# BREW_MONITOR.net
KiCad netlist of a schematic drawn in Altium Designer
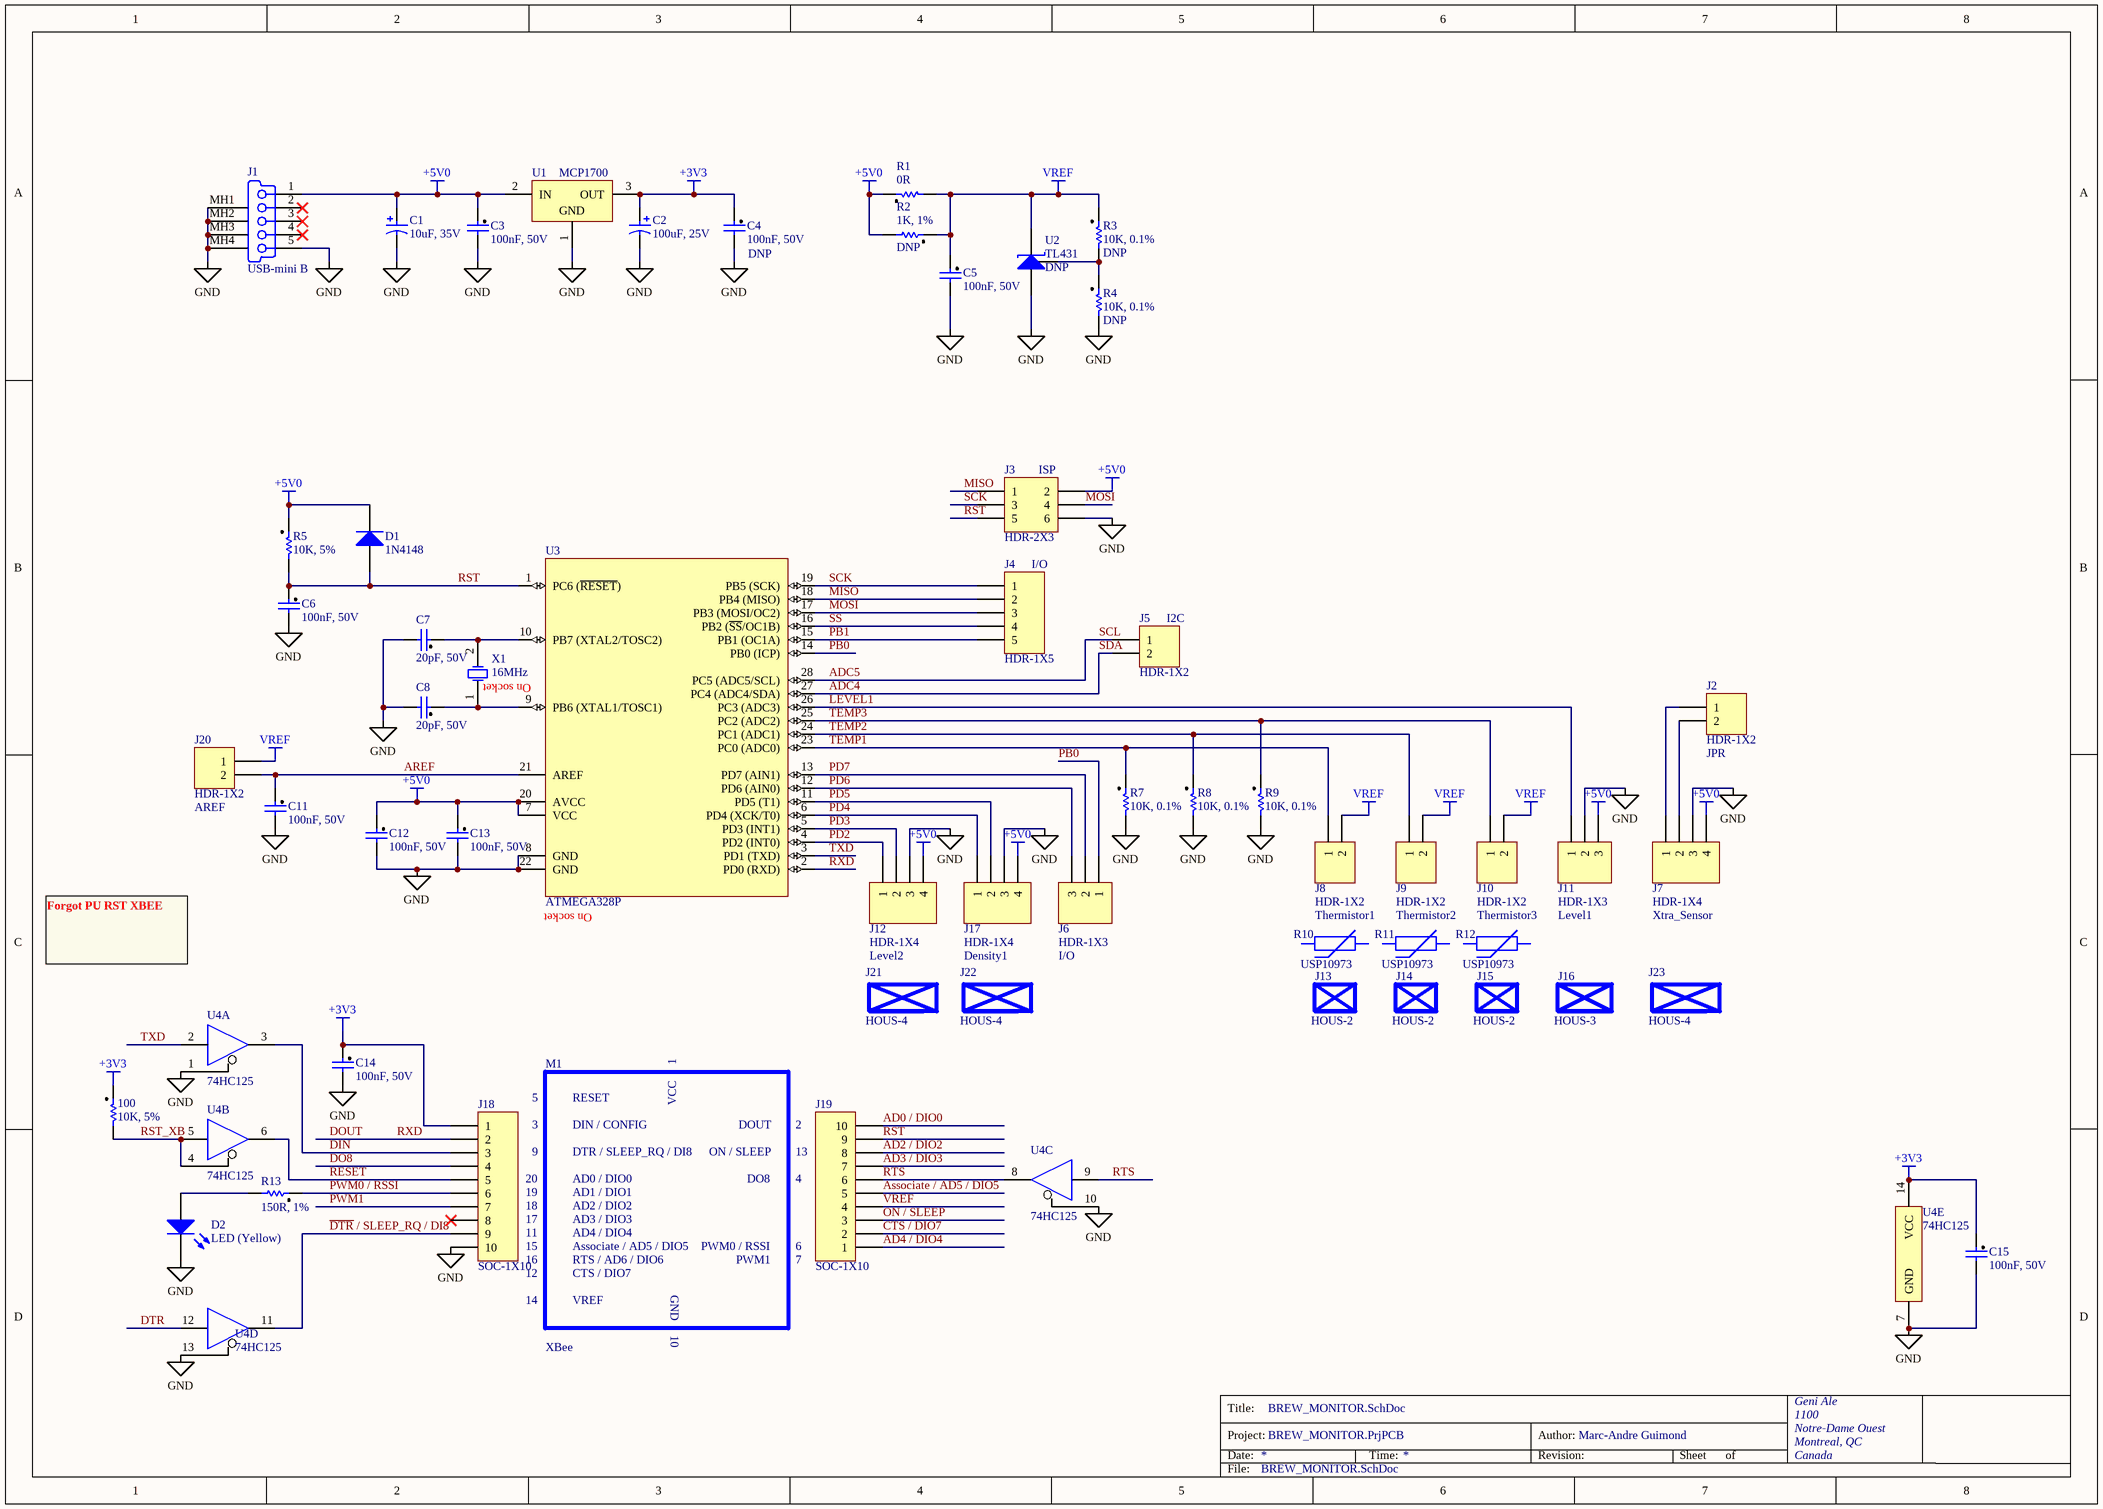
[diagram p0: BREW_MONITOR.SchDoc]

(export (version "E")
  (design (tool "Eeschema 10.0.6"))
  (components
    (comp (ref "100")
      (value "10K, 5%")
      (footprint "0805 (2012 Metric)")
      (description "RES 10K OHM 1/8W 5% 0805")
      (fields (field (name "MANUFACTURER") "Stackpole Electronics Inc") (field (name "TOLERANCE") "5%"))
      (libsource (lib "GRR_Resistor") (part "RMCF0805JT10K0"))
    )
    (comp (ref "C1")
      (value "10uF, 35V")
      (footprint "CAP_RAD-2.0")
      (description "CAP ALUM 10UF 35V 20% RADIAL")
      (fields (field (name "MANUFACTURER") "Kemet") (field (name "VOLTAGE") "35V"))
      (libsource (lib "GRR_Capacitor") (part "ESK106M035AC3AA"))
    )
    (comp (ref "C2")
      (value "100uF, 25V")
      (footprint "CAP_RAD-2.0")
      (description "CAP ALUM 100UF 25V 20% RADIAL")
      (fields (field (name "MANUFACTURER") "Kemet") (field (name "VOLTAGE") "25V"))
      (libsource (lib "GRR_Capacitor") (part "ESK107M025AC3AA"))
    )
    (comp (ref "C3")
      (value "100nF, 50V")
      (footprint "0805 (2012 Metric)")
      (description "CAP CER 0.1UF 50V 10% X7R 0805")
      (fields (field (name "MANUFACTURER") "TDK Corporation") (field (name "VOLTAGE") "50V"))
      (libsource (lib "GRR_Capacitor") (part "C2012X7R1H104K085AA"))
    )
    (comp (ref "C4")
      (value "100nF, 50V")
      (footprint "0805 (2012 Metric)")
      (description "CAP CER 0.1UF 50V 10% X7R 0805")
      (fields
        (field (name "MANUFACTURER") "TDK Corporation")
        (field (name "VOLTAGE") "50V")
        (field (name "POPULATE") "DNP")
      )
      (libsource (lib "GRR_Capacitor") (part "C2012X7R1H104K085AA"))
    )
    (comp (ref "C5")
      (value "100nF, 50V")
      (footprint "0805 (2012 Metric)")
      (description "CAP CER 0.1UF 50V 10% X7R 0805")
      (fields (field (name "MANUFACTURER") "TDK Corporation") (field (name "VOLTAGE") "50V"))
      (libsource (lib "GRR_Capacitor") (part "C2012X7R1H104K085AA"))
    )
    (comp (ref "C6")
      (value "100nF, 50V")
      (footprint "0805 (2012 Metric)")
      (description "CAP CER 0.1UF 50V 10% X7R 0805")
      (fields (field (name "MANUFACTURER") "TDK Corporation") (field (name "VOLTAGE") "50V"))
      (libsource (lib "GRR_Capacitor") (part "C2012X7R1H104K085AA"))
    )
    (comp (ref "C7")
      (value "20pF, 50V")
      (footprint "0603 (1608 Metric)")
      (description "CAP CER 20PF 50V 5% NPO 0603")
      (fields (field (name "MANUFACTURER") "Yageo") (field (name "VOLTAGE") "50V"))
      (libsource (lib "GRR_Capacitor") (part "CC0603JRNPO9BN200"))
    )
    (comp (ref "C8")
      (value "20pF, 50V")
      (footprint "0603 (1608 Metric)")
      (description "CAP CER 20PF 50V 5% NPO 0603")
      (fields (field (name "MANUFACTURER") "Yageo") (field (name "VOLTAGE") "50V"))
      (libsource (lib "GRR_Capacitor") (part "CC0603JRNPO9BN200"))
    )
    (comp (ref "C11")
      (value "100nF, 50V")
      (footprint "0805 (2012 Metric)")
      (description "CAP CER 0.1UF 50V 10% X7R 0805")
      (fields (field (name "MANUFACTURER") "TDK Corporation") (field (name "VOLTAGE") "50V"))
      (libsource (lib "GRR_Capacitor") (part "C2012X7R1H104K085AA"))
    )
    (comp (ref "C12")
      (value "100nF, 50V")
      (footprint "0805 (2012 Metric)")
      (description "CAP CER 0.1UF 50V 10% X7R 0805")
      (fields (field (name "MANUFACTURER") "TDK Corporation") (field (name "VOLTAGE") "50V"))
      (libsource (lib "GRR_Capacitor") (part "C2012X7R1H104K085AA"))
    )
    (comp (ref "C13")
      (value "100nF, 50V")
      (footprint "0805 (2012 Metric)")
      (description "CAP CER 0.1UF 50V 10% X7R 0805")
      (fields (field (name "MANUFACTURER") "TDK Corporation") (field (name "VOLTAGE") "50V"))
      (libsource (lib "GRR_Capacitor") (part "C2012X7R1H104K085AA"))
    )
    (comp (ref "C14")
      (value "100nF, 50V")
      (footprint "0805 (2012 Metric)")
      (description "CAP CER 0.1UF 50V 10% X7R 0805")
      (fields (field (name "MANUFACTURER") "TDK Corporation") (field (name "VOLTAGE") "50V"))
      (libsource (lib "GRR_Capacitor") (part "C2012X7R1H104K085AA"))
    )
    (comp (ref "C15")
      (value "100nF, 50V")
      (footprint "0805 (2012 Metric)")
      (description "CAP CER 0.1UF 50V 10% X7R 0805")
      (fields (field (name "MANUFACTURER") "TDK Corporation") (field (name "VOLTAGE") "50V"))
      (libsource (lib "GRR_Capacitor") (part "C2012X7R1H104K085AA"))
    )
    (comp (ref "D1")
      (value "1N4148")
      (footprint "DO-35")
      (description "DIODE SMALL SIG 100V 0.2A DO35")
      (fields (field (name "MANUFACTURER") "Fairchild Semiconductor"))
      (libsource (lib "GRR_Diode") (part "1N4148TACT"))
    )
    (comp (ref "D2")
      (value "LED (Yellow)")
      (footprint "LED-1")
      (description "LED 5MM YELLOW DIFFUSED")
      (fields (field (name "MANUFACTURER") "Lite-On Inc"))
      (libsource (lib "GRR_LED") (part "LTL-307Y"))
    )
    (comp (ref "J1")
      (value "USB-mini B")
      (footprint "CON_USB-UX60SC")
      (description "CONN RCPT USB MINI B R/A SMD")
      (fields (field (name "MANUFACTURER") "Hirose Electric Co Ltd"))
      (libsource (lib "GRR_Connector") (part "UX60SC-MB-5ST(80)"))
    )
    (comp (ref "J2")
      (value "HDR-1X2")
      (footprint "HDR1X2")
      (description "CONN HEADER .100\" SNGL STR 2POS")
      (fields (field (name "MANUFACTURER") "Sullins Connector Solutions") (field (name "REF") "JPR"))
      (libsource (lib "GRR_Connector") (part "PRPC002SAAN-RC"))
    )
    (comp (ref "J3")
      (value "HDR-2X3")
      (footprint "HDR2X3")
      (description "JUMPER PLUG 6POS DOUBLE ROW")
      (fields (field (name "MANUFACTURER") "Omron Electronics Inc-EMC Div"))
      (libsource (lib "GRR_Connector") (part "XG8T-0631"))
    )
    (comp (ref "J4")
      (value "HDR-1X5")
      (footprint "HDR1X5")
      (description "CONN HEADER .100\" SNGL STR 5POS")
      (fields (field (name "MANUFACTURER") "Sullins Connector Solutions") (field (name "REF") "I/O"))
      (libsource (lib "GRR_Connector") (part "PRPC005SAAN-RC"))
    )
    (comp (ref "J5")
      (value "HDR-1X2")
      (footprint "HDR1X2")
      (description "CONN HEADER .100\" SNGL STR 2POS")
      (fields (field (name "MANUFACTURER") "Sullins Connector Solutions") (field (name "REF") "I2C"))
      (libsource (lib "GRR_Connector") (part "PRPC002SAAN-RC"))
    )
    (comp (ref "J6")
      (value "HDR-1X3")
      (footprint "HDR1X3")
      (description "CONN HEADER .100\" SNGL STR 3POS")
      (fields (field (name "MANUFACTURER") "Sullins Connector Solutions") (field (name "REF") "I/O"))
      (libsource (lib "GRR_Connector") (part "PRPC003SAAN-RC"))
    )
    (comp (ref "J7")
      (value "HDR-1X4")
      (footprint "HDR1X4_RA POL_SHR_TE")
      (description "CONN HEADER RTANG 4POS .100 TIN")
      (fields (field (name "MANUFACTURER") "TE Connectivity") (field (name "REF") "Xtra_Sensor"))
      (libsource (lib "GRR_Connector") (part "2-644488-4"))
    )
    (comp (ref "J8")
      (value "HDR-1X2")
      (footprint "HDR1X2_RA POL_SHR_TE")
      (description "CONN HEADER RTANG 2POS .100 TIN")
      (fields (field (name "MANUFACTURER") "TE Connectivity") (field (name "REF") "Thermistor1"))
      (libsource (lib "GRR_Connector") (part "2-644488-2"))
    )
    (comp (ref "J9")
      (value "HDR-1X2")
      (footprint "HDR1X2_RA POL_SHR_TE")
      (description "CONN HEADER RTANG 2POS .100 TIN")
      (fields (field (name "MANUFACTURER") "TE Connectivity") (field (name "REF") "Thermistor2"))
      (libsource (lib "GRR_Connector") (part "2-644488-2"))
    )
    (comp (ref "J10")
      (value "HDR-1X2")
      (footprint "HDR1X2_RA POL_SHR_TE")
      (description "CONN HEADER RTANG 2POS .100 TIN")
      (fields (field (name "MANUFACTURER") "TE Connectivity") (field (name "REF") "Thermistor3"))
      (libsource (lib "GRR_Connector") (part "2-644488-2"))
    )
    (comp (ref "J11")
      (value "HDR-1X3")
      (footprint "HDR1X3_RA POL_SHR_TE")
      (description "CONN HEADER RTANG 3POS .100 TIN")
      (fields (field (name "MANUFACTURER") "TE Connectivity") (field (name "REF") "Level1"))
      (libsource (lib "GRR_Connector") (part "2-644488-3"))
    )
    (comp (ref "J12")
      (value "HDR-1X4")
      (footprint "HDR1X4_RA POL_SHR_TE")
      (description "CONN HEADER RTANG 4POS .100 TIN")
      (fields (field (name "MANUFACTURER") "TE Connectivity") (field (name "REF") "Level2"))
      (libsource (lib "GRR_Connector") (part "2-644488-4"))
    )
    (comp (ref "J13")
      (value "HOUS-2")
      (footprint "NO_FOOT")
      (description "CONN RCPT 2POS 22AWG POL MTA100")
      (fields (field (name "MANUFACTURER") "TE Connectivity"))
      (libsource (lib "GRR_CrimpTerminal") (part "3-644083-2"))
    )
    (comp (ref "J14")
      (value "HOUS-2")
      (footprint "NO_FOOT")
      (description "CONN RCPT 2POS 22AWG POL MTA100")
      (fields (field (name "MANUFACTURER") "TE Connectivity"))
      (libsource (lib "GRR_CrimpTerminal") (part "3-644083-2"))
    )
    (comp (ref "J15")
      (value "HOUS-2")
      (footprint "NO_FOOT")
      (description "CONN RCPT 2POS 22AWG POL MTA100")
      (fields (field (name "MANUFACTURER") "TE Connectivity"))
      (libsource (lib "GRR_CrimpTerminal") (part "3-644083-2"))
    )
    (comp (ref "J16")
      (value "HOUS-3")
      (footprint "NO_FOOT")
      (description "CONN RCPT 3POS 22AWG POL MTA100")
      (fields (field (name "MANUFACTURER") "TE Connectivity"))
      (libsource (lib "GRR_CrimpTerminal") (part "3-644083-3"))
    )
    (comp (ref "J17")
      (value "HDR-1X4")
      (footprint "HDR1X4_RA POL_SHR_TE")
      (description "CONN HEADER RTANG 4POS .100 TIN")
      (fields (field (name "MANUFACTURER") "TE Connectivity") (field (name "REF") "Density1"))
      (libsource (lib "GRR_Connector") (part "2-644488-4"))
    )
    (comp (ref "J18")
      (value "SOC-1X10")
      (footprint "SOC1X10 2MM")
      (description "CONN SOCKET 10POS 2MM VERT T/H")
      (fields (field (name "MANUFACTURER") "3M"))
      (libsource (lib "GRR_Connector") (part "950510-6102-AR"))
    )
    (comp (ref "J19")
      (value "SOC-1X10")
      (footprint "SOC1X10 2MM")
      (description "CONN SOCKET 10POS 2MM VERT T/H")
      (fields (field (name "MANUFACTURER") "3M"))
      (libsource (lib "") (part "950510-6102-AR_1"))
    )
    (comp (ref "J20")
      (value "HDR-1X2")
      (footprint "HDR1X2")
      (description "CONN HEADER .100\" SNGL STR 2POS")
      (fields (field (name "MANUFACTURER") "Sullins Connector Solutions") (field (name "REF") "AREF"))
      (libsource (lib "") (part "PRPC002SAAN-RC_1"))
    )
    (comp (ref "J21")
      (value "HOUS-4")
      (footprint "NO_FOOT")
      (description "CONN RCPT 4POS 22AWG POL MTA100")
      (fields (field (name "MANUFACTURER") "TE Connectivity"))
      (libsource (lib "GRR_CrimpTerminal") (part "3-644083-4"))
    )
    (comp (ref "J22")
      (value "HOUS-4")
      (footprint "NO_FOOT")
      (description "CONN RCPT 4POS 22AWG POL MTA100")
      (fields (field (name "MANUFACTURER") "TE Connectivity"))
      (libsource (lib "GRR_CrimpTerminal") (part "3-644083-4"))
    )
    (comp (ref "J23")
      (value "HOUS-4")
      (footprint "NO_FOOT")
      (description "CONN RCPT 4POS 22AWG POL MTA100")
      (fields (field (name "MANUFACTURER") "TE Connectivity"))
      (libsource (lib "GRR_CrimpTerminal") (part "3-644083-4"))
    )
    (comp (ref "M1")
      (value "XBee")
      (footprint "XBee-20")
      (description "MODULE 802.15.4 1MW W/WIRE ANT")
      (fields (field (name "MANUFACTURER") "Digi International/Maxstream"))
      (libsource (lib "GRR_RF") (part "XB24-AWI-001"))
    )
    (comp (ref "R1")
      (value "0R")
      (footprint "JPR-0.2")
      (description "RES 0R")
      (fields (field (name "POWER") "0.333W, 1/3W"))
      (libsource (lib "GRR_Resistor") (part "JUMPER"))
    )
    (comp (ref "R2")
      (value "1K, 1%")
      (footprint "0805 (2012 Metric)")
      (description "RES 1K OHM 1/8W 1% 0805")
      (fields
        (field (name "MANUFACTURER") "Stackpole Electronics Inc")
        (field (name "TOLERANCE") "1%")
        (field (name "POPULATE") "DNP")
      )
      (libsource (lib "GRR_Resistor") (part "RMCF0805FT1K00"))
    )
    (comp (ref "R3")
      (value "10K, 0.1%")
      (footprint "0805 (2012 Metric)")
      (description "RES 10K OHM 1/8W .1% 0805 SMD")
      (fields
        (field (name "MANUFACTURER") "Bourns Inc.")
        (field (name "TOLERANCE") "0.1%")
        (field (name "POPULATE") "DNP")
      )
      (libsource (lib "GRR_Resistor") (part "CRT0805-BY-1002ELF"))
    )
    (comp (ref "R4")
      (value "10K, 0.1%")
      (footprint "0805 (2012 Metric)")
      (description "RES 10K OHM 1/8W .1% 0805 SMD")
      (fields
        (field (name "MANUFACTURER") "Bourns Inc.")
        (field (name "TOLERANCE") "0.1%")
        (field (name "POPULATE") "DNP")
      )
      (libsource (lib "GRR_Resistor") (part "CRT0805-BY-1002ELF"))
    )
    (comp (ref "R5")
      (value "10K, 5%")
      (footprint "0805 (2012 Metric)")
      (description "RES 10K OHM 1/8W 5% 0805")
      (fields (field (name "MANUFACTURER") "Stackpole Electronics Inc") (field (name "TOLERANCE") "5%"))
      (libsource (lib "GRR_Resistor") (part "RMCF0805JT10K0"))
    )
    (comp (ref "R7")
      (value "10K, 0.1%")
      (footprint "0805 (2012 Metric)")
      (description "RES 10K OHM 1/8W .1% 0805 SMD")
      (fields (field (name "MANUFACTURER") "Bourns Inc.") (field (name "TOLERANCE") "0.1%"))
      (libsource (lib "GRR_Resistor") (part "CRT0805-BY-1002ELF"))
    )
    (comp (ref "R8")
      (value "10K, 0.1%")
      (footprint "0805 (2012 Metric)")
      (description "RES 10K OHM 1/8W .1% 0805 SMD")
      (fields (field (name "MANUFACTURER") "Bourns Inc.") (field (name "TOLERANCE") "0.1%"))
      (libsource (lib "GRR_Resistor") (part "CRT0805-BY-1002ELF"))
    )
    (comp (ref "R9")
      (value "10K, 0.1%")
      (footprint "0805 (2012 Metric)")
      (description "RES 10K OHM 1/8W .1% 0805 SMD")
      (fields (field (name "MANUFACTURER") "Bourns Inc.") (field (name "TOLERANCE") "0.1%"))
      (libsource (lib "GRR_Resistor") (part "CRT0805-BY-1002ELF"))
    )
    (comp (ref "R10")
      (value "USP10973")
      (footprint "NO_FOOT")
      (description "THERMISTOR ASSEMBLY 10K OHM")
      (fields (field (name "MANUFACTURER") "US Sensor") (field (name "TOLERANCE") "±1%"))
      (libsource (lib "GRR_Sensor") (part "USP10973"))
    )
    (comp (ref "R11")
      (value "USP10973")
      (footprint "NO_FOOT")
      (description "THERMISTOR ASSEMBLY 10K OHM")
      (fields (field (name "MANUFACTURER") "US Sensor") (field (name "TOLERANCE") "±1%"))
      (libsource (lib "GRR_Sensor") (part "USP10973"))
    )
    (comp (ref "R12")
      (value "USP10973")
      (footprint "NO_FOOT")
      (description "THERMISTOR ASSEMBLY 10K OHM")
      (fields (field (name "MANUFACTURER") "US Sensor") (field (name "TOLERANCE") "±1%"))
      (libsource (lib "GRR_Sensor") (part "USP10973"))
    )
    (comp (ref "R13")
      (value "150R, 1%")
      (footprint "0805 (2012 Metric)")
      (description "RES 150 OHM 1/8W 1% 0805")
      (fields (field (name "MANUFACTURER") "Stackpole Electronics Inc") (field (name "TOLERANCE") "1%"))
      (libsource (lib "GRR_Resistor") (part "RMCF0805FT150R"))
    )
    (comp (ref "U1")
      (value "MCP1700")
      (footprint "TO-92A_L")
      (description "IC REG LDO 3.3V 0.25A TO92-3")
      (fields (field (name "MANUFACTURER") "Microchip Technology"))
      (libsource (lib "GRR_PMIC") (part "MCP1700-3302E/TO"))
    )
    (comp (ref "U2")
      (value "TL431")
      (footprint "TO-92A_L")
      (description "IC VREF SHUNT PREC ADJ TO-92-3")
      (fields
        (field (name "MANUFACTURER") "STMicroelectronics")
        (field (name "TOLERANCE") "±2%")
        (field (name "POPULATE") "DNP")
      )
      (libsource (lib "GRR_PMIC") (part "TL431CZ"))
    )
    (comp (ref "U3")
      (value "ATMEGA328P")
      (footprint "DIP-28")
      (description "IC MCU 8BIT 32KB FLASH 28DIP")
      (fields (field (name "MANUFACTURER") "Atmel"))
      (libsource (lib "GRR_IC") (part "ATMEGA328P-PU"))
    )
    (comp (ref "U4")
      (value "74HC125")
      (footprint "DIP-14")
      (description "IC BUS BUFFER TRI-ST QD 14DIP")
      (fields (field (name "MANUFACTURER") "Texas Instruments"))
      (libsource (lib "GRR_IC") (part "SN74AHC125N"))
    )
    (comp (ref "X1")
      (value "16MHz")
      (footprint "HC49U")
      (description "CRYSTAL16MHZ 20PF THRU")
      (fields (field (name "MANUFACTURER") "Fox Electronics"))
      (libsource (lib "GRR_Resonator") (part "FOXLF160-20"))
    )
  )
  (nets
    (net (code "1") (name "+3V3") (class "Default")
      (node (ref "100") (pin "1") (pinfunction "1_1") (pintype "passive"))
      (node (ref "C14") (pin "1") (pinfunction "1_1") (pintype "passive"))
      (node (ref "C15") (pin "1") (pinfunction "1_1") (pintype "passive"))
      (node (ref "C2") (pin "1") (pinfunction "1_1") (pintype "passive"))
      (node (ref "C4") (pin "1") (pinfunction "1_1") (pintype "passive"))
      (node (ref "J18") (pin "1") (pinfunction "1_1") (pintype "passive"))
      (node (ref "U1") (pin "3") (pinfunction "OUT_3") (pintype "power_in"))
      (node (ref "U4") (pin "14") (pinfunction "VCC_14") (pintype "power_in"))
    )
    (net (code "2") (name "+5V0") (class "Default")
      (node (ref "C1") (pin "1") (pinfunction "1_1") (pintype "passive"))
      (node (ref "C12") (pin "1") (pinfunction "1_1") (pintype "passive"))
      (node (ref "C13") (pin "1") (pinfunction "1_1") (pintype "passive"))
      (node (ref "C3") (pin "1") (pinfunction "1_1") (pintype "passive"))
      (node (ref "D1") (pin "2") (pinfunction "K_2") (pintype "passive"))
      (node (ref "J1") (pin "1") (pinfunction "V_BUS_(5V)_1") (pintype "passive"))
      (node (ref "J11") (pin "3") (pinfunction "3_3") (pintype "passive"))
      (node (ref "J12") (pin "4") (pinfunction "4_4") (pintype "passive"))
      (node (ref "J17") (pin "4") (pinfunction "4_4") (pintype "passive"))
      (node (ref "J3") (pin "2") (pinfunction "2_2") (pintype "passive"))
      (node (ref "J7") (pin "4") (pinfunction "4_4") (pintype "passive"))
      (node (ref "R1") (pin "1") (pinfunction "1_1") (pintype "passive"))
      (node (ref "R2") (pin "2") (pinfunction "2_2") (pintype "passive"))
      (node (ref "R5") (pin "1") (pinfunction "1_1") (pintype "passive"))
      (node (ref "U1") (pin "2") (pinfunction "IN_2") (pintype "power_in"))
      (node (ref "U3") (pin "20") (pinfunction "AVCC_20") (pintype "power_in"))
      (node (ref "U3") (pin "7") (pinfunction "VCC_7") (pintype "power_in"))
    )
    (net (code "3") (name "/AD0 {slash} DIO0") (class "Default")
      (node (ref "J19") (pin "10") (pinfunction "10_10") (pintype "passive"))
    )
    (net (code "4") (name "/AD2 {slash} DIO2") (class "Default")
      (node (ref "J19") (pin "8") (pinfunction "8_8") (pintype "passive"))
    )
    (net (code "5") (name "/AD3 {slash} DIO3") (class "Default")
      (node (ref "J19") (pin "7") (pinfunction "7_7") (pintype "passive"))
    )
    (net (code "6") (name "/AD4 {slash} DIO4") (class "Default")
      (node (ref "J19") (pin "1") (pinfunction "1_1") (pintype "passive"))
    )
    (net (code "7") (name "/ADC4") (class "Default")
      (node (ref "J5") (pin "2") (pinfunction "2_2") (pintype "passive"))
      (node (ref "U3") (pin "27") (pinfunction "PC4_(ADC4/SDA)_27") (pintype "bidirectional"))
    )
    (net (code "8") (name "/ADC5") (class "Default")
      (node (ref "J5") (pin "1") (pinfunction "1_1") (pintype "passive"))
      (node (ref "U3") (pin "28") (pinfunction "PC5_(ADC5/SCL)_28") (pintype "bidirectional"))
    )
    (net (code "9") (name "/AREF") (class "Default")
      (node (ref "C11") (pin "1") (pinfunction "1_1") (pintype "passive"))
      (node (ref "J20") (pin "2") (pinfunction "2_2") (pintype "passive"))
      (node (ref "U3") (pin "21") (pinfunction "AREF_21") (pintype "passive"))
    )
    (net (code "10") (name "/Associate {slash} AD5 {slash} DIO5") (class "Default")
      (node (ref "J19") (pin "5") (pinfunction "5_5") (pintype "passive"))
    )
    (net (code "11") (name "/DIN") (class "Default")
      (node (ref "J18") (pin "3") (pinfunction "3_3") (pintype "passive"))
      (node (ref "U4") (pin "3") (pinfunction "Y1_3") (pintype "tri_state"))
    )
    (net (code "12") (name "/DO8") (class "Default")
      (node (ref "J18") (pin "4") (pinfunction "4_4") (pintype "passive"))
    )
    (net (code "13") (name "/DOUT") (class "Default")
      (node (ref "J18") (pin "2") (pinfunction "2_2") (pintype "passive"))
      (node (ref "U3") (pin "2") (pinfunction "PD0_(RXD)_2") (pintype "bidirectional"))
    )
    (net (code "14") (name "/DTR") (class "Default")
      (node (ref "U4") (pin "12") (pinfunction "A4_12") (pintype "passive"))
    )
    (net (code "15") (name "/LEVEL1") (class "Default")
      (node (ref "J11") (pin "1") (pinfunction "1_1") (pintype "passive"))
      (node (ref "U3") (pin "26") (pinfunction "PC3_(ADC3)_26") (pintype "bidirectional"))
    )
    (net (code "16") (name "/MISO") (class "Default")
      (node (ref "J3") (pin "1") (pinfunction "1_1") (pintype "passive"))
      (node (ref "J4") (pin "2") (pinfunction "2_2") (pintype "passive"))
      (node (ref "U3") (pin "18") (pinfunction "PB4_(MISO)_18") (pintype "bidirectional"))
    )
    (net (code "17") (name "/MOSI") (class "Default")
      (node (ref "J3") (pin "4") (pinfunction "4_4") (pintype "passive"))
      (node (ref "J4") (pin "3") (pinfunction "3_3") (pintype "passive"))
      (node (ref "U3") (pin "17") (pinfunction "PB3_(MOSI/OC2)_17") (pintype "bidirectional"))
    )
    (net (code "18") (name "/ON {slash} SLEEP") (class "Default")
      (node (ref "J19") (pin "3") (pinfunction "3_3") (pintype "passive"))
    )
    (net (code "19") (name "/PB0") (class "Default")
      (node (ref "J6") (pin "1") (pinfunction "1_1") (pintype "passive"))
      (node (ref "U3") (pin "14") (pinfunction "PB0_(ICP)_14") (pintype "bidirectional"))
    )
    (net (code "20") (name "/PB1") (class "Default")
      (node (ref "J4") (pin "5") (pinfunction "5_5") (pintype "passive"))
      (node (ref "U3") (pin "15") (pinfunction "PB1_(OC1A)_15") (pintype "bidirectional"))
    )
    (net (code "21") (name "/PD2") (class "Default")
      (node (ref "J12") (pin "1") (pinfunction "1_1") (pintype "passive"))
      (node (ref "U3") (pin "4") (pinfunction "PD2_(INT0)_4") (pintype "bidirectional"))
    )
    (net (code "22") (name "/PD3") (class "Default")
      (node (ref "J12") (pin "2") (pinfunction "2_2") (pintype "passive"))
      (node (ref "U3") (pin "5") (pinfunction "PD3_(INT1)_5") (pintype "bidirectional"))
    )
    (net (code "23") (name "/PD4") (class "Default")
      (node (ref "J17") (pin "1") (pinfunction "1_1") (pintype "passive"))
      (node (ref "U3") (pin "6") (pinfunction "PD4_(XCK/T0)_6") (pintype "bidirectional"))
    )
    (net (code "24") (name "/PD5") (class "Default")
      (node (ref "J17") (pin "2") (pinfunction "2_2") (pintype "passive"))
      (node (ref "U3") (pin "11") (pinfunction "PD5_(T1)_11") (pintype "bidirectional"))
    )
    (net (code "25") (name "/PD6") (class "Default")
      (node (ref "J6") (pin "3") (pinfunction "3_3") (pintype "passive"))
      (node (ref "U3") (pin "12") (pinfunction "PD6_(AIN0)_12") (pintype "bidirectional"))
    )
    (net (code "26") (name "/PD7") (class "Default")
      (node (ref "J6") (pin "2") (pinfunction "2_2") (pintype "passive"))
      (node (ref "U3") (pin "13") (pinfunction "PD7_(AIN1)_13") (pintype "bidirectional"))
    )
    (net (code "27") (name "/PWM0 {slash} RSSI") (class "Default")
      (node (ref "J18") (pin "6") (pinfunction "6_6") (pintype "passive"))
      (node (ref "R13") (pin "1") (pinfunction "1_1") (pintype "passive"))
    )
    (net (code "28") (name "/PWM1") (class "Default")
      (node (ref "J18") (pin "7") (pinfunction "7_7") (pintype "passive"))
    )
    (net (code "29") (name "/RESET") (class "Default")
      (node (ref "J18") (pin "5") (pinfunction "5_5") (pintype "passive"))
      (node (ref "U4") (pin "6") (pinfunction "Y2_6") (pintype "tri_state"))
    )
    (net (code "30") (name "/RST") (class "Default")
      (node (ref "C6") (pin "1") (pinfunction "1_1") (pintype "passive"))
      (node (ref "D1") (pin "1") (pinfunction "A_1") (pintype "passive"))
      (node (ref "J19") (pin "9") (pinfunction "9_9") (pintype "passive"))
      (node (ref "J3") (pin "5") (pinfunction "5_5") (pintype "passive"))
      (node (ref "R5") (pin "2") (pinfunction "2_2") (pintype "passive"))
      (node (ref "U3") (pin "1") (pinfunction "PC6_(~{RESET})_1") (pintype "bidirectional"))
    )
    (net (code "31") (name "/RST_XB") (class "Default")
      (node (ref "100") (pin "2") (pinfunction "2_2") (pintype "passive"))
      (node (ref "U4") (pin "4") (pinfunction "~{OE}2_4") (pintype "passive"))
      (node (ref "U4") (pin "5") (pinfunction "A2_5") (pintype "passive"))
    )
    (net (code "32") (name "/RTS") (class "Default")
      (node (ref "U4") (pin "9") (pinfunction "A3_9") (pintype "passive"))
    )
    (net (code "33") (name "/SCK") (class "Default")
      (node (ref "J3") (pin "3") (pinfunction "3_3") (pintype "passive"))
      (node (ref "J4") (pin "1") (pinfunction "1_1") (pintype "passive"))
      (node (ref "U3") (pin "19") (pinfunction "PB5_(SCK)_19") (pintype "bidirectional"))
    )
    (net (code "34") (name "/SS") (class "Default")
      (node (ref "J4") (pin "4") (pinfunction "4_4") (pintype "passive"))
      (node (ref "U3") (pin "16") (pinfunction "PB2_(~{SS}/OC1B)_16") (pintype "bidirectional"))
    )
    (net (code "35") (name "/TEMP1") (class "Default")
      (node (ref "J8") (pin "1") (pinfunction "1_1") (pintype "passive"))
      (node (ref "R7") (pin "1") (pinfunction "1_1") (pintype "passive"))
      (node (ref "U3") (pin "23") (pinfunction "PC0_(ADC0)_23") (pintype "bidirectional"))
    )
    (net (code "36") (name "/TEMP2") (class "Default")
      (node (ref "J9") (pin "1") (pinfunction "1_1") (pintype "passive"))
      (node (ref "R8") (pin "1") (pinfunction "1_1") (pintype "passive"))
      (node (ref "U3") (pin "24") (pinfunction "PC1_(ADC1)_24") (pintype "bidirectional"))
    )
    (net (code "37") (name "/TEMP3") (class "Default")
      (node (ref "J10") (pin "1") (pinfunction "1_1") (pintype "passive"))
      (node (ref "R9") (pin "1") (pinfunction "1_1") (pintype "passive"))
      (node (ref "U3") (pin "25") (pinfunction "PC2_(ADC2)_25") (pintype "bidirectional"))
    )
    (net (code "38") (name "/TXD") (class "Default")
      (node (ref "U3") (pin "3") (pinfunction "PD1_(TXD)_3") (pintype "bidirectional"))
      (node (ref "U4") (pin "2") (pinfunction "A1_2") (pintype "passive"))
    )
    (net (code "39") (name "/~{CTS} {slash} DIO7") (class "Default")
      (node (ref "J19") (pin "2") (pinfunction "2_2") (pintype "passive"))
    )
    (net (code "40") (name "/~{DTR} {slash} SLEEP_RQ {slash} DI8") (class "Default")
      (node (ref "J18") (pin "9") (pinfunction "9_9") (pintype "passive"))
      (node (ref "U4") (pin "11") (pinfunction "Y4_11") (pintype "tri_state"))
    )
    (net (code "41") (name "/~{RTS}") (class "Default")
      (node (ref "J19") (pin "6") (pinfunction "6_6") (pintype "passive"))
      (node (ref "U4") (pin "8") (pinfunction "Y3_8") (pintype "tri_state"))
    )
    (net (code "42") (name "GND") (class "Default")
      (node (ref "C1") (pin "2") (pinfunction "2_2") (pintype "passive"))
      (node (ref "C11") (pin "2") (pinfunction "2_2") (pintype "passive"))
      (node (ref "C12") (pin "2") (pinfunction "2_2") (pintype "passive"))
      (node (ref "C13") (pin "2") (pinfunction "2_2") (pintype "passive"))
      (node (ref "C14") (pin "2") (pinfunction "2_2") (pintype "passive"))
      (node (ref "C15") (pin "2") (pinfunction "2_2") (pintype "passive"))
      (node (ref "C2") (pin "2") (pinfunction "2_2") (pintype "passive"))
      (node (ref "C3") (pin "2") (pinfunction "2_2") (pintype "passive"))
      (node (ref "C4") (pin "2") (pinfunction "2_2") (pintype "passive"))
      (node (ref "C5") (pin "2") (pinfunction "2_2") (pintype "passive"))
      (node (ref "C6") (pin "2") (pinfunction "2_2") (pintype "passive"))
      (node (ref "C7") (pin "2") (pinfunction "2_2") (pintype "passive"))
      (node (ref "C8") (pin "2") (pinfunction "2_2") (pintype "passive"))
      (node (ref "D2") (pin "2") (pinfunction "K_2") (pintype "passive"))
      (node (ref "J1") (pin "5") (pinfunction "GND_5") (pintype "passive"))
      (node (ref "J1") (pin "MH1") (pinfunction "Tab_MH1") (pintype "passive"))
      (node (ref "J1") (pin "MH2") (pinfunction "Tab_MH2") (pintype "passive"))
      (node (ref "J1") (pin "MH3") (pinfunction "Tab_MH3") (pintype "passive"))
      (node (ref "J1") (pin "MH4") (pinfunction "Tab_MH4") (pintype "passive"))
      (node (ref "J11") (pin "2") (pinfunction "2_2") (pintype "passive"))
      (node (ref "J12") (pin "3") (pinfunction "3_3") (pintype "passive"))
      (node (ref "J17") (pin "3") (pinfunction "3_3") (pintype "passive"))
      (node (ref "J18") (pin "10") (pinfunction "10_10") (pintype "passive"))
      (node (ref "J3") (pin "6") (pinfunction "6_6") (pintype "passive"))
      (node (ref "J7") (pin "3") (pinfunction "3_3") (pintype "passive"))
      (node (ref "R4") (pin "2") (pinfunction "2_2") (pintype "passive"))
      (node (ref "R7") (pin "2") (pinfunction "2_2") (pintype "passive"))
      (node (ref "R8") (pin "2") (pinfunction "2_2") (pintype "passive"))
      (node (ref "R9") (pin "2") (pinfunction "2_2") (pintype "passive"))
      (node (ref "U1") (pin "1") (pinfunction "ADJ_1") (pintype "power_in"))
      (node (ref "U2") (pin "2") (pinfunction "A_2") (pintype "passive"))
      (node (ref "U3") (pin "22") (pinfunction "GND_22") (pintype "power_in"))
      (node (ref "U3") (pin "8") (pinfunction "GND_8") (pintype "power_in"))
      (node (ref "U4") (pin "1") (pinfunction "~{OE}1_1") (pintype "passive"))
      (node (ref "U4") (pin "10") (pinfunction "~{OE}3_10") (pintype "passive"))
      (node (ref "U4") (pin "13") (pinfunction "~{OE}4_13") (pintype "passive"))
      (node (ref "U4") (pin "7") (pinfunction "GND_7") (pintype "power_in"))
    )
    (net (code "43") (name "Net-(D2-A)") (class "Default")
      (node (ref "D2") (pin "1") (pinfunction "A_1") (pintype "passive"))
      (node (ref "R13") (pin "2") (pinfunction "2_2") (pintype "passive"))
    )
    (net (code "44") (name "Net-(J2-Pad1)") (class "Default")
      (node (ref "J2") (pin "1") (pinfunction "1_1") (pintype "passive"))
      (node (ref "J7") (pin "1") (pinfunction "1_1") (pintype "passive"))
    )
    (net (code "45") (name "Net-(J2-Pad2)") (class "Default")
      (node (ref "J2") (pin "2") (pinfunction "2_2") (pintype "passive"))
      (node (ref "J7") (pin "2") (pinfunction "2_2") (pintype "passive"))
    )
    (net (code "46") (name "Net-(U2-REF)") (class "Default")
      (node (ref "R3") (pin "2") (pinfunction "2_2") (pintype "passive"))
      (node (ref "R4") (pin "1") (pinfunction "1_1") (pintype "passive"))
      (node (ref "U2") (pin "1") (pinfunction "REF_1") (pintype "passive"))
    )
    (net (code "47") (name "Net-(U3-PB6_(XTAL1{slash}TOSC1))") (class "Default")
      (node (ref "C8") (pin "1") (pinfunction "1_1") (pintype "passive"))
      (node (ref "U3") (pin "9") (pinfunction "PB6_(XTAL1/TOSC1)_9") (pintype "bidirectional"))
      (node (ref "X1") (pin "1") (pinfunction "OSC1_1") (pintype "passive"))
    )
    (net (code "48") (name "Net-(U3-PB7_(XTAL2{slash}TOSC2))") (class "Default")
      (node (ref "C7") (pin "1") (pinfunction "1_1") (pintype "passive"))
      (node (ref "U3") (pin "10") (pinfunction "PB7_(XTAL2/TOSC2)_10") (pintype "bidirectional"))
      (node (ref "X1") (pin "2") (pinfunction "OSC2_2") (pintype "passive"))
    )
    (net (code "49") (name "VREF") (class "Default")
      (node (ref "C5") (pin "1") (pinfunction "1_1") (pintype "passive"))
      (node (ref "J10") (pin "2") (pinfunction "2_2") (pintype "passive"))
      (node (ref "J19") (pin "4") (pinfunction "4_4") (pintype "passive"))
      (node (ref "J20") (pin "1") (pinfunction "1_1") (pintype "passive"))
      (node (ref "J8") (pin "2") (pinfunction "2_2") (pintype "passive"))
      (node (ref "J9") (pin "2") (pinfunction "2_2") (pintype "passive"))
      (node (ref "R1") (pin "2") (pinfunction "2_2") (pintype "passive"))
      (node (ref "R2") (pin "1") (pinfunction "1_1") (pintype "passive"))
      (node (ref "R3") (pin "1") (pinfunction "1_1") (pintype "passive"))
      (node (ref "U2") (pin "3") (pinfunction "K_3") (pintype "passive"))
    )
    (net (code "50") (name "unconnected-(J1-D+-Pad3)") (class "Default")
      (node (ref "J1") (pin "3") (pinfunction "D+_3") (pintype "passive+no_connect"))
    )
    (net (code "51") (name "unconnected-(J1-D--Pad2)") (class "Default")
      (node (ref "J1") (pin "2") (pinfunction "D-_2") (pintype "passive+no_connect"))
    )
    (net (code "52") (name "unconnected-(J1-NC-Pad4)") (class "Default")
      (node (ref "J1") (pin "4") (pinfunction "NC_4") (pintype "passive+no_connect"))
    )
    (net (code "53") (name "unconnected-(J18-Pad8)") (class "Default")
      (node (ref "J18") (pin "8") (pinfunction "8_8") (pintype "passive+no_connect"))
    )
  )
)
